# iCliQ_v1.net
KiCad netlist of a schematic drawn in Altium Designer
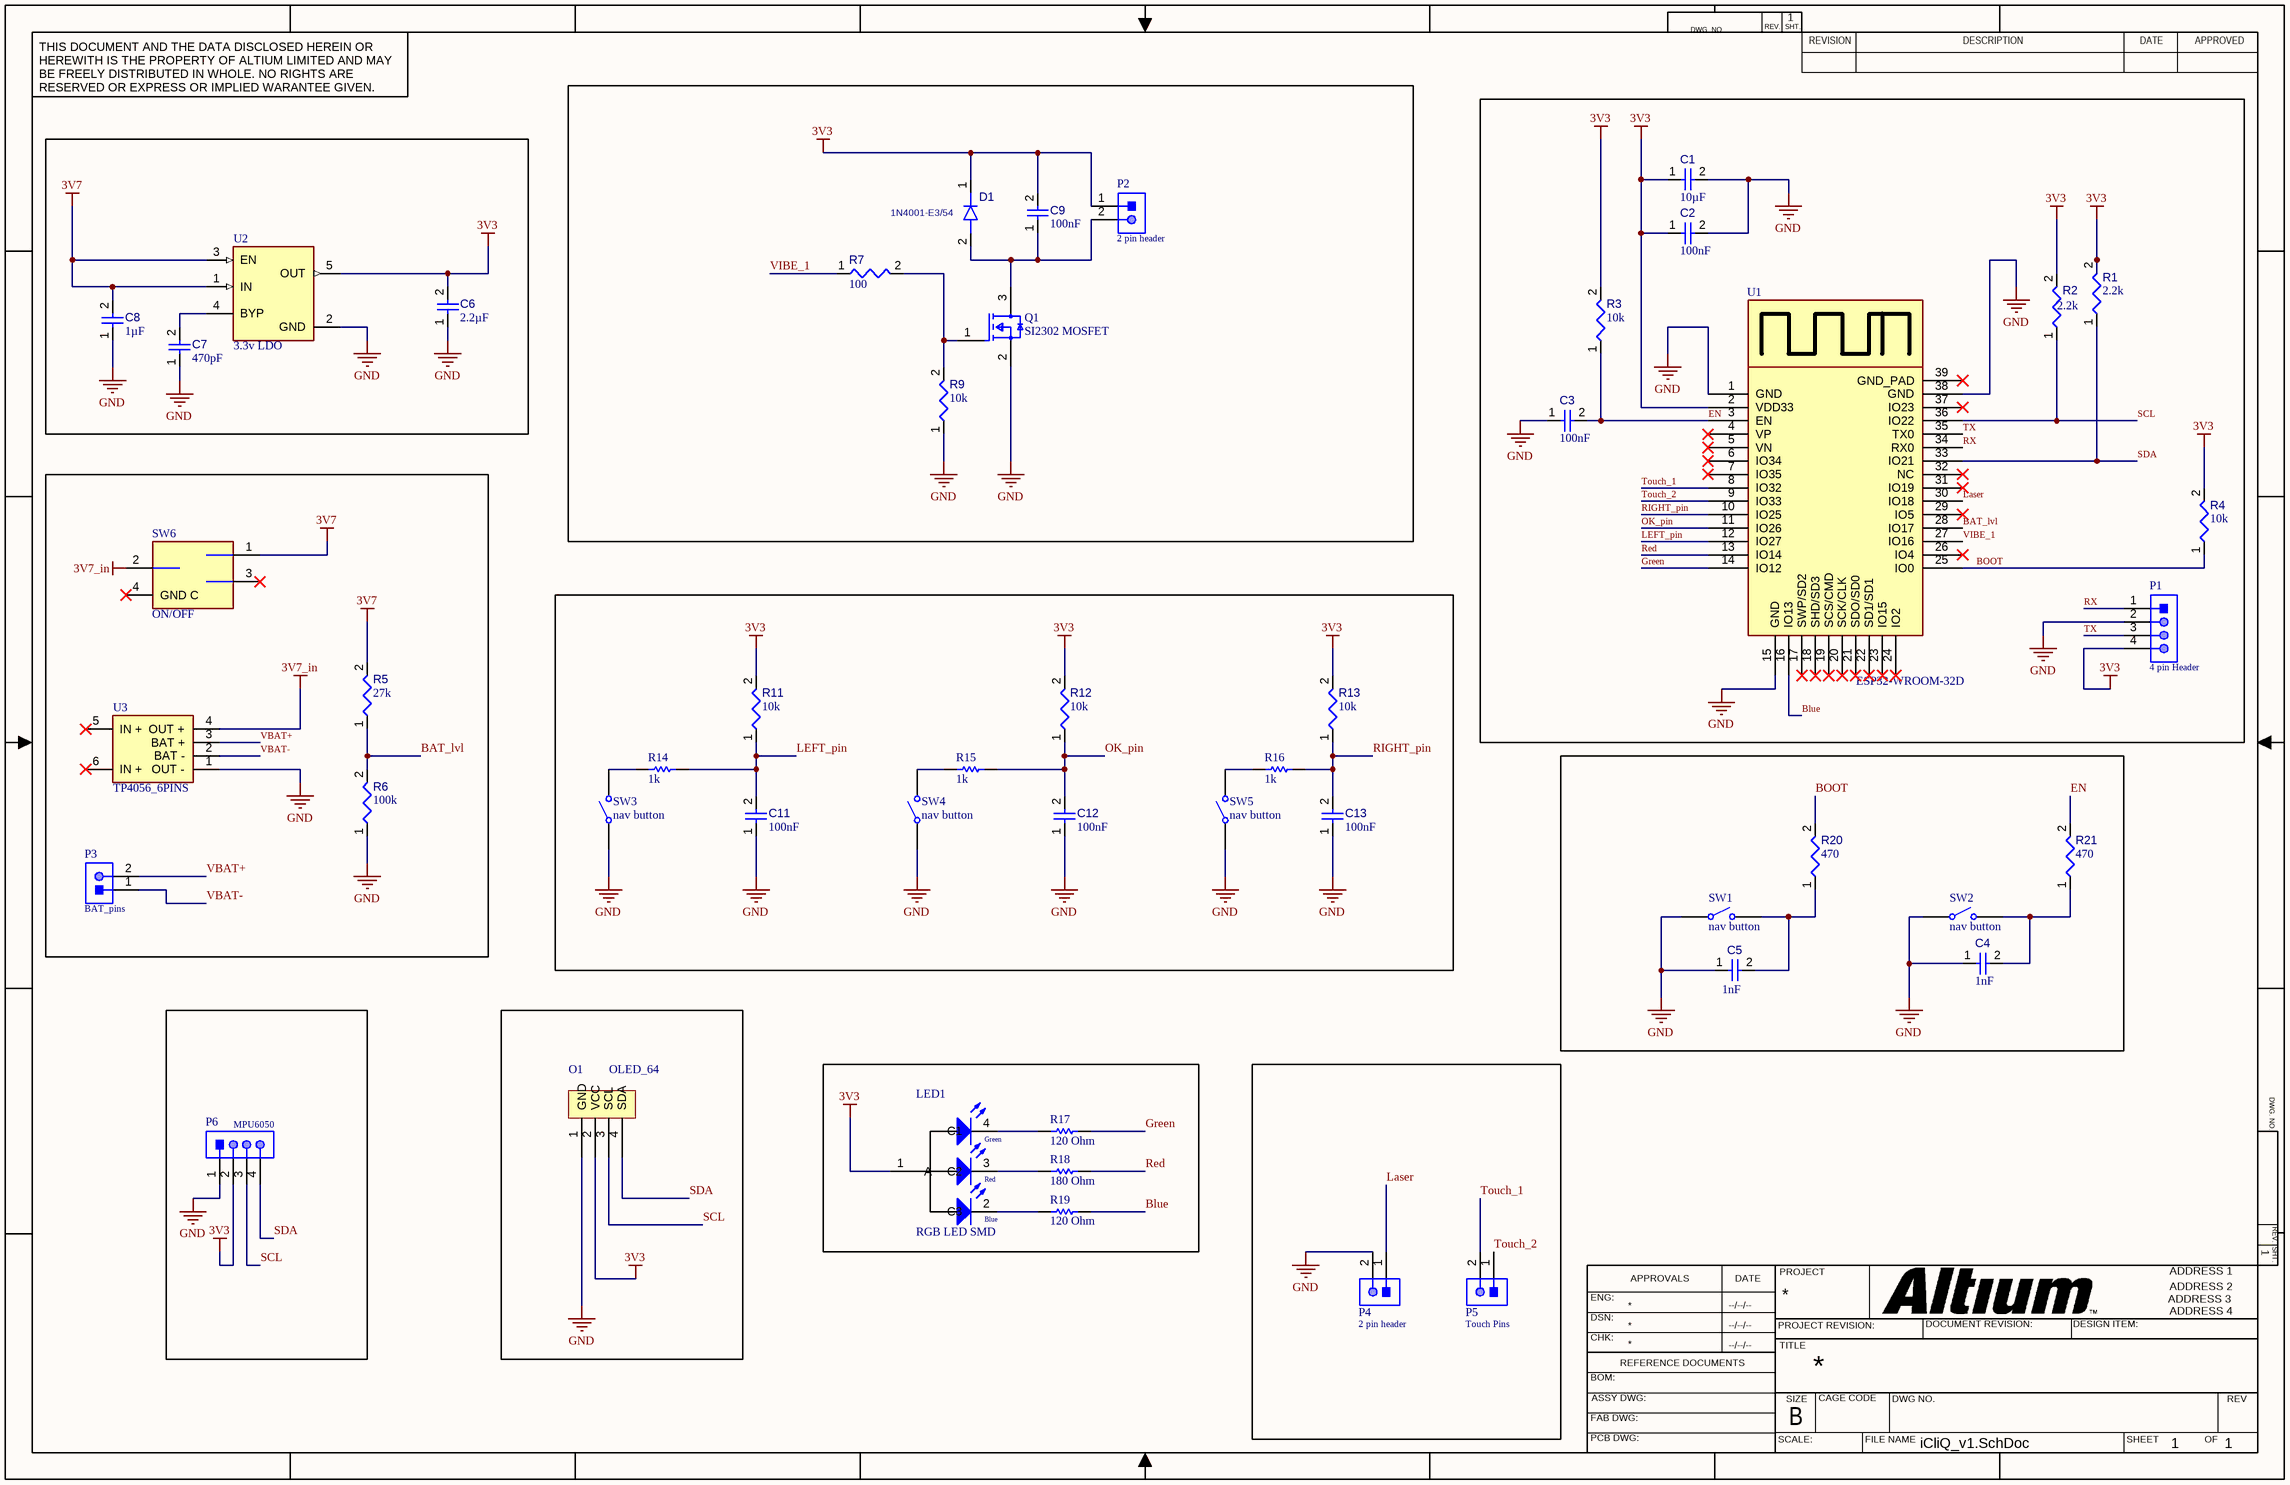
[diagram p0: iCliQ_v1.SchDoc]

(export (version "E")
  (design (tool "Eeschema 10.0.6"))
  (components
    (comp (ref "C1")
      (value "10µF")
      (footprint "FP-C0805C-DG-IPC_A")
      (fields (field (name "Comment") "10uF 10V 0805"))
      (libsource (lib "Company of Noobs - ENTC") (part "CAP-NP-2"))
    )
    (comp (ref "C2")
      (value "100nF")
      (footprint "CAPC2013X95X50LL10T25")
      (description "Chip Capacitor, 100 nF, +/- 10%, 50 V, 0805 (2012 Metric)")
      (fields (field (name "TOLERANCE") "10%") (field (name "Comment") "Capacitor 100 nF +/-10% 50 V 0805"))
      (libsource (lib "Company of Noobs - ENTC") (part "CAP-NP-2"))
    )
    (comp (ref "C3")
      (value "100nF")
      (footprint "CAPC2013X95X50LL10T25")
      (description "Chip Capacitor, 100 nF, +/- 10%, 50 V, 0805 (2012 Metric)")
      (fields (field (name "TOLERANCE") "10%") (field (name "Comment") "Capacitor 100 nF +/-10% 50 V 0805"))
      (libsource (lib "Company of Noobs - ENTC") (part "CAP-NP-2"))
    )
    (comp (ref "C4")
      (value "1nF")
      (footprint "FP-C0805C-DN-IPC_A")
      (fields (field (name "Comment") "1 nF 50V 0805"))
      (libsource (lib "Company of Noobs - ENTC") (part "CAP-NP-2"))
    )
    (comp (ref "C5")
      (value "1nF")
      (footprint "FP-C0805C-DN-IPC_A")
      (fields (field (name "Comment") "1 nF 50V 0805"))
      (libsource (lib "Company of Noobs - ENTC") (part "CAP-NP-2"))
    )
    (comp (ref "C6")
      (value "2.2µF")
      (footprint "FP-C0805C225K4RACAUTO-IPC_A")
      (fields (field (name "Comment") "2.2 uF 0805"))
      (libsource (lib "Company of Noobs - ENTC") (part "CAP-NP-2"))
    )
    (comp (ref "C7")
      (value "470pF")
      (footprint "FP-C0805C-DN-IPC_A")
      (fields (field (name "Comment") "470 pF 0805"))
      (libsource (lib "Company of Noobs - ENTC") (part "CAP-NP-2"))
    )
    (comp (ref "C8")
      (value "1µF")
      (footprint "CAPC2013X140X50LL20T25")
      (fields (field (name "Comment") "1uF 10V 0805"))
      (libsource (lib "Company of Noobs - ENTC") (part "CAP-NP-2"))
    )
    (comp (ref "C9")
      (value "100nF")
      (footprint "CAPC2013X95X50LL10T25")
      (description "Chip Capacitor, 100 nF, +/- 10%, 50 V, 0805 (2012 Metric)")
      (fields (field (name "TOLERANCE") "10%") (field (name "Comment") "Capacitor 100 nF +/-10% 50 V 0805"))
      (libsource (lib "Company of Noobs - ENTC") (part "CAP-NP-2"))
    )
    (comp (ref "C11")
      (value "100nF")
      (footprint "CAPC2013X95X50LL10T25")
      (description "Chip Capacitor, 100 nF, +/- 10%, 50 V, 0805 (2012 Metric)")
      (fields (field (name "TOLERANCE") "10%") (field (name "Comment") "Capacitor 100 nF +/-10% 50 V 0805"))
      (libsource (lib "Company of Noobs - ENTC") (part "CAP-NP-2"))
    )
    (comp (ref "C12")
      (value "100nF")
      (footprint "CAPC2013X95X50LL10T25")
      (description "Chip Capacitor, 100 nF, +/- 10%, 50 V, 0805 (2012 Metric)")
      (fields (field (name "TOLERANCE") "10%") (field (name "Comment") "Capacitor 100 nF +/-10% 50 V 0805"))
      (libsource (lib "Company of Noobs - ENTC") (part "CAP-NP-2"))
    )
    (comp (ref "C13")
      (value "100nF")
      (footprint "CAPC2013X95X50LL10T25")
      (description "Chip Capacitor, 100 nF, +/- 10%, 50 V, 0805 (2012 Metric)")
      (fields (field (name "TOLERANCE") "10%") (field (name "Comment") "Capacitor 100 nF +/-10% 50 V 0805"))
      (libsource (lib "Company of Noobs - ENTC") (part "CAP-NP-2"))
    )
    (comp (ref "D1")
      (value "1N4001-E3/54")
      (footprint "FP-1N4001-E3-54-MFG")
      (description "Rectifier Diode, 1 Phase, 1 Element, 1A, 50V V(RRM), Silicon, DO-204AL")
      (libsource (lib "Company of Noobs - ENTC") (part "DIODE-2"))
    )
    (comp (ref "LED1")
      (value "RGB LED SMD")
      (footprint "3528_A")
      (description "Triple Color LED, Red/green/blue, Water Clear")
      (libsource (lib "Company of Noobs - ENTC") (part "WE-LED_RGB_A1B2R3G4-4"))
    )
    (comp (ref "O1")
      (value "OLED_64")
      (footprint "OLED_SSD1306_64")
      (description "JST (JAPAN SOLDERLESS TERMINALS) - B8B-XH-A (LF)(SN) - HEADER, VERTICAL, 8WAY")
      (fields
        (field (name "MANUFACTURER") "JST")
        (field (name "MANUFACTURER PART NUMBER") "B8B-XH-A(LF)(SN)")
      )
      (libsource (lib "Schlib1") (part "OLED_64"))
    )
    (comp (ref "P1")
      (value "4 pin Header")
      (footprint "61300411121")
      (libsource (lib "") (part "WE-CN-1P-M-R4_1"))
    )
    (comp (ref "P2")
      (value "2 pin header")
      (footprint "61300211121")
      (libsource (lib "") (part "WE-CN-1P-M-R2_2"))
    )
    (comp (ref "P3")
      (value "BAT_pins")
      (footprint "61300211121")
      (libsource (lib "") (part "WE-CN-1P-M-R2_1"))
    )
    (comp (ref "P4")
      (value "2 pin header")
      (footprint "61300211121")
      (libsource (lib "Company of Noobs - ENTC") (part "WE-CN-1P-M-R2"))
    )
    (comp (ref "P5")
      (value "Touch Pins")
      (footprint "61300211121")
      (libsource (lib "Company of Noobs - ENTC") (part "WE-CN-1P-M-R2"))
    )
    (comp (ref "P6")
      (value "MPU6050")
      (footprint "61300411121")
      (libsource (lib "Company of Noobs - ENTC") (part "WE-CN-1P-M-R4"))
    )
    (comp (ref "Q1")
      (value "SI2302 MOSFET")
      (footprint "FP-S-03946-MFG")
      (libsource (lib "Company of Noobs - ENTC") (part "0a9ea7c96deaaede766a5b531c28de0"))
    )
    (comp (ref "R1")
      (value "2.2k")
      (footprint "RESC2013X60X40LL20T25")
      (description "Fixed Resistor, Thin Film, 0.125W, 2200ohm, 100V, 0.5% +/-Tol, 25ppm/Cel, Surface Mount, 0805")
      (fields (field (name "TOLERANCE") "0.5%") (field (name "POWER") "125mW"))
      (libsource (lib "Company of Noobs - ENTC") (part "RES-2"))
    )
    (comp (ref "R2")
      (value "2.2k")
      (footprint "RESC2013X60X40LL20T25")
      (description "Fixed Resistor, Thin Film, 0.125W, 2200ohm, 100V, 0.5% +/-Tol, 25ppm/Cel, Surface Mount, 0805")
      (fields (field (name "TOLERANCE") "0.5%") (field (name "POWER") "125mW"))
      (libsource (lib "Company of Noobs - ENTC") (part "RES-2"))
    )
    (comp (ref "R3")
      (value "10k")
      (footprint "RESC2013X60X35LL10T20")
      (fields
        (field (name "TOLERANCE") "1%")
        (field (name "POWER") "125mW")
        (field (name "Comment") "10K 0805")
      )
      (libsource (lib "Company of Noobs - ENTC") (part "RES-2"))
    )
    (comp (ref "R4")
      (value "10k")
      (footprint "RESC2013X60X35LL10T20")
      (fields
        (field (name "TOLERANCE") "1%")
        (field (name "POWER") "125mW")
        (field (name "Comment") "10K 0805")
      )
      (libsource (lib "Company of Noobs - ENTC") (part "RES-2"))
    )
    (comp (ref "R5")
      (value "27k")
      (footprint "RESC2013X60X40LL20T25")
      (description "Fixed Resistor, Thin Film, 0.125W, 27000ohm, 100V, 0.1% +/-Tol, 25ppm/Cel, Surface Mount, 0805")
      (fields (field (name "POWER") "125mW") (field (name "TOLERANCE") "0.1%"))
      (libsource (lib "Company of Noobs - ENTC") (part "RES-2"))
    )
    (comp (ref "R6")
      (value "100k")
      (footprint "RESC2013X70X40ML20T20")
      (description "Chip Resistor, 100 KOhm, +/- 1%, 0.125 W, -55 to 155 degC, 0805 (2012 Metric)")
      (fields (field (name "POWER") "125mW") (field (name "TOLERANCE") "1%"))
      (libsource (lib "Company of Noobs - ENTC") (part "RES-2"))
    )
    (comp (ref "R7")
      (value "100")
      (footprint "RESC2013X60X40LL20T25")
      (description "Fixed Resistor, Thin Film, 0.125W, 100ohm, 100V, 0.1% +/-Tol, 25ppm/Cel, Surface Mount, 0805")
      (fields (field (name "POWER") "125mW") (field (name "TOLERANCE") "0.1%"))
      (libsource (lib "Company of Noobs - ENTC") (part "RES-2"))
    )
    (comp (ref "R9")
      (value "10k")
      (footprint "RESC2013X60X35LL10T20")
      (fields
        (field (name "TOLERANCE") "1%")
        (field (name "POWER") "125mW")
        (field (name "Comment") "10K 0805")
      )
      (libsource (lib "Company of Noobs - ENTC") (part "RES-2"))
    )
    (comp (ref "R11")
      (value "10k")
      (footprint "RESC2013X60X35LL10T20")
      (fields
        (field (name "TOLERANCE") "1%")
        (field (name "POWER") "125mW")
        (field (name "Comment") "10K 0805")
      )
      (libsource (lib "Company of Noobs - ENTC") (part "RES-2"))
    )
    (comp (ref "R12")
      (value "10k")
      (footprint "RESC2013X60X35LL10T20")
      (fields
        (field (name "TOLERANCE") "1%")
        (field (name "POWER") "125mW")
        (field (name "Comment") "10K 0805")
      )
      (libsource (lib "Company of Noobs - ENTC") (part "RES-2"))
    )
    (comp (ref "R13")
      (value "10k")
      (footprint "RESC2013X60X35LL10T20")
      (fields
        (field (name "TOLERANCE") "1%")
        (field (name "POWER") "125mW")
        (field (name "Comment") "10K 0805")
      )
      (libsource (lib "Company of Noobs - ENTC") (part "RES-2"))
    )
    (comp (ref "R14")
      (value "1k")
      (footprint "RESC2013X70X40NL20T20")
      (fields
        (field (name "TOLERANCE") "5%")
        (field (name "POWER") "500mW")
        (field (name "Comment") "Resistor 1K +/-5% 0805 500 mW.")
      )
      (libsource (lib "Company of Noobs - ENTC") (part "RES"))
    )
    (comp (ref "R15")
      (value "1k")
      (footprint "RESC2013X70X40NL20T20")
      (fields
        (field (name "TOLERANCE") "5%")
        (field (name "POWER") "500mW")
        (field (name "Comment") "Resistor 1K +/-5% 0805 500 mW.")
      )
      (libsource (lib "Company of Noobs - ENTC") (part "RES"))
    )
    (comp (ref "R16")
      (value "1k")
      (footprint "RESC2013X70X40NL20T20")
      (fields
        (field (name "TOLERANCE") "5%")
        (field (name "POWER") "500mW")
        (field (name "Comment") "Resistor 1K +/-5% 0805 500 mW.")
      )
      (libsource (lib "Company of Noobs - ENTC") (part "RES"))
    )
    (comp (ref "R17")
      (value "120 Ohm")
      (footprint "RESC2013X50X35ML15T15")
      (description "Chip Resistor, 0 Ohm, +/- 1%, 125 mW, -55 to 155 degC, 0805 (2012 Metric)")
      (fields (field (name "TOLERANCE") "1%") (field (name "POWER") "125mW"))
      (libsource (lib "") (part "RES-2_1"))
    )
    (comp (ref "R18")
      (value "180 Ohm")
      (footprint "RESC2013X50X35ML15T15")
      (description "Chip Resistor, 0 Ohm, +/- 1%, 125 mW, -55 to 155 degC, 0805 (2012 Metric)")
      (fields (field (name "TOLERANCE") "1%") (field (name "POWER") "125mW"))
      (libsource (lib "") (part "RES-2_1"))
    )
    (comp (ref "R19")
      (value "120 Ohm")
      (footprint "RESC2013X50X35ML15T15")
      (description "Chip Resistor, 0 Ohm, +/- 1%, 125 mW, -55 to 155 degC, 0805 (2012 Metric)")
      (fields (field (name "TOLERANCE") "1%") (field (name "POWER") "125mW"))
      (libsource (lib "") (part "RES-2_1"))
    )
    (comp (ref "R20")
      (value "470")
      (footprint "RESC0805(2012)_L")
      (description "Chip Resistor, 470 Ohms, +/-5%, 125 mW, -55 to 155 degC, 0805")
      (fields (field (name "TOLERANCE") "5%") (field (name "POWER") "125mW"))
      (libsource (lib "Company of Noobs - ENTC") (part "RES-2"))
    )
    (comp (ref "R21")
      (value "470")
      (footprint "RESC0805(2012)_L")
      (description "Chip Resistor, 470 Ohms, +/-5%, 125 mW, -55 to 155 degC, 0805")
      (fields (field (name "TOLERANCE") "5%") (field (name "POWER") "125mW"))
      (libsource (lib "Company of Noobs - ENTC") (part "RES-2"))
    )
    (comp (ref "SW1")
      (value "nav button")
      (footprint "434121050816")
      (libsource (lib "Company of Noobs - ENTC") (part "WE-TACT-SW-2"))
    )
    (comp (ref "SW2")
      (value "nav button")
      (footprint "434121050816")
      (libsource (lib "Company of Noobs - ENTC") (part "WE-TACT-SW-2"))
    )
    (comp (ref "SW3")
      (value "nav button")
      (footprint "434121050816")
      (libsource (lib "Company of Noobs - ENTC") (part "WE-TACT-SW-2"))
    )
    (comp (ref "SW4")
      (value "nav button")
      (footprint "434121050816")
      (libsource (lib "Company of Noobs - ENTC") (part "WE-TACT-SW-2"))
    )
    (comp (ref "SW5")
      (value "nav button")
      (footprint "434121050816")
      (libsource (lib "Company of Noobs - ENTC") (part "WE-TACT-SW-2"))
    )
    (comp (ref "SW6")
      (value "Switch_ALPS_SSSS811101_eec")
      (footprint "ALPS_SSSS811101_0")
      (fields
        (field (name "MANUFACTURER") "ALPS")
        (field (name "MOUSER PART NUMBER") "688-SSSS811101")
        (field (name "PART NUMBER") "ON/OFF")
      )
      (libsource (lib "Switch_ALPS_SSSS811101_eec") (part "Switch_ALPS_SSSS811101_eec"))
    )
    (comp (ref "U1")
      (value "ESP32-WROOM-32D")
      (footprint "ESP32-WROOM-32D")
      (description "Chip SMD 39 Pads Wifi 2.4GHz BLE 4.2 18x25.5mm w/ Antenna.")
      (libsource (lib "Company of Noobs - ENTC") (part "ESP32-WROOM-32D"))
    )
    (comp (ref "U2")
      (value "3.3v LDO")
      (footprint "FP-SOT23-5LD-PL-1-MFG")
      (description "IC REG LDO 3.3V 0.5A SOT23-5")
      (libsource (lib "Company of Noobs - ENTC") (part "16b36b16d6b7b40c29ab14718bc3058"))
    )
    (comp (ref "U3")
      (value "TP4056_6PINS")
      (footprint "TP4056_6PINs")
      (description "MODULE BATTERY CHARGER 6 PINS")
      (fields (field (name "SOURCE") "Random.SchLib"))
      (libsource (lib "Company of Noobs - ENTC") (part "TP4056_6PINS"))
    )
  )
  (nets
    (net (code "1") (name "/BAT_lvl") (class "Default")
      (node (ref "R5") (pin "1") (pinfunction "1_1") (pintype "passive"))
      (node (ref "R6") (pin "2") (pinfunction "2_2") (pintype "passive"))
      (node (ref "U1") (pin "28") (pinfunction "IO17_28") (pintype "passive"))
    )
    (net (code "2") (name "/BOOT") (class "Default")
      (node (ref "R20") (pin "2") (pinfunction "2_2") (pintype "passive"))
      (node (ref "R4") (pin "1") (pinfunction "1_1") (pintype "passive"))
      (node (ref "U1") (pin "25") (pinfunction "IO0_25") (pintype "passive"))
    )
    (net (code "3") (name "/Blue") (class "Default")
      (node (ref "R19") (pin "2") (pinfunction "2_2") (pintype "passive"))
      (node (ref "U1") (pin "16") (pinfunction "IO13_16") (pintype "passive"))
    )
    (net (code "4") (name "/EN") (class "Default")
      (node (ref "C3") (pin "2") (pinfunction "2_2") (pintype "passive"))
      (node (ref "R21") (pin "2") (pinfunction "2_2") (pintype "passive"))
      (node (ref "R3") (pin "1") (pinfunction "1_1") (pintype "passive"))
      (node (ref "U1") (pin "3") (pinfunction "EN_3") (pintype "passive"))
    )
    (net (code "5") (name "/Green") (class "Default")
      (node (ref "R17") (pin "2") (pinfunction "2_2") (pintype "passive"))
      (node (ref "U1") (pin "14") (pinfunction "IO12_14") (pintype "passive"))
    )
    (net (code "6") (name "/LEFT_pin") (class "Default")
      (node (ref "C11") (pin "2") (pinfunction "2_2") (pintype "passive"))
      (node (ref "R11") (pin "1") (pinfunction "1_1") (pintype "passive"))
      (node (ref "R14") (pin "2") (pinfunction "2_2") (pintype "passive"))
      (node (ref "U1") (pin "12") (pinfunction "IO27_12") (pintype "passive"))
    )
    (net (code "7") (name "/Laser") (class "Default")
      (node (ref "P4") (pin "1") (pinfunction "1_1") (pintype "passive"))
      (node (ref "U1") (pin "30") (pinfunction "IO18_30") (pintype "passive"))
    )
    (net (code "8") (name "/OK_pin") (class "Default")
      (node (ref "C12") (pin "2") (pinfunction "2_2") (pintype "passive"))
      (node (ref "R12") (pin "1") (pinfunction "1_1") (pintype "passive"))
      (node (ref "R15") (pin "2") (pinfunction "2_2") (pintype "passive"))
      (node (ref "U1") (pin "11") (pinfunction "IO26_11") (pintype "passive"))
    )
    (net (code "9") (name "/RIGHT_pin") (class "Default")
      (node (ref "C13") (pin "2") (pinfunction "2_2") (pintype "passive"))
      (node (ref "R13") (pin "1") (pinfunction "1_1") (pintype "passive"))
      (node (ref "R16") (pin "2") (pinfunction "2_2") (pintype "passive"))
      (node (ref "U1") (pin "10") (pinfunction "IO25_10") (pintype "passive"))
    )
    (net (code "10") (name "/RX") (class "Default")
      (node (ref "P1") (pin "1") (pinfunction "1_1") (pintype "passive"))
      (node (ref "U1") (pin "34") (pinfunction "RX0_34") (pintype "passive"))
    )
    (net (code "11") (name "/Red") (class "Default")
      (node (ref "R18") (pin "2") (pinfunction "2_2") (pintype "passive"))
      (node (ref "U1") (pin "13") (pinfunction "IO14_13") (pintype "passive"))
    )
    (net (code "12") (name "/SCL") (class "Default")
      (node (ref "O1") (pin "3") (pinfunction "SCL_3") (pintype "passive"))
      (node (ref "P6") (pin "3") (pinfunction "3_3") (pintype "passive"))
      (node (ref "R2") (pin "1") (pinfunction "1_1") (pintype "passive"))
      (node (ref "U1") (pin "36") (pinfunction "IO22_36") (pintype "passive"))
    )
    (net (code "13") (name "/SDA") (class "Default")
      (node (ref "O1") (pin "4") (pinfunction "SDA_4") (pintype "passive"))
      (node (ref "P6") (pin "4") (pinfunction "4_4") (pintype "passive"))
      (node (ref "R1") (pin "1") (pinfunction "1_1") (pintype "passive"))
      (node (ref "U1") (pin "33") (pinfunction "IO21_33") (pintype "passive"))
    )
    (net (code "14") (name "/TX") (class "Default")
      (node (ref "P1") (pin "3") (pinfunction "3_3") (pintype "passive"))
      (node (ref "U1") (pin "35") (pinfunction "TX0_35") (pintype "passive"))
    )
    (net (code "15") (name "/Touch_1") (class "Default")
      (node (ref "P5") (pin "2") (pinfunction "2_2") (pintype "passive"))
      (node (ref "U1") (pin "8") (pinfunction "IO32_8") (pintype "passive"))
    )
    (net (code "16") (name "/Touch_2") (class "Default")
      (node (ref "P5") (pin "1") (pinfunction "1_1") (pintype "passive"))
      (node (ref "U1") (pin "9") (pinfunction "IO33_9") (pintype "passive"))
    )
    (net (code "17") (name "/VBAT+") (class "Default")
      (node (ref "P3") (pin "2") (pinfunction "2_2") (pintype "passive"))
      (node (ref "U3") (pin "3") (pinfunction "BAT_+_3") (pintype "passive"))
    )
    (net (code "18") (name "/VBAT-") (class "Default")
      (node (ref "P3") (pin "1") (pinfunction "1_1") (pintype "passive"))
      (node (ref "U3") (pin "2") (pinfunction "BAT_-_2") (pintype "passive"))
    )
    (net (code "19") (name "/VIBE_1") (class "Default")
      (node (ref "R7") (pin "1") (pinfunction "1_1") (pintype "passive"))
      (node (ref "U1") (pin "27") (pinfunction "IO16_27") (pintype "passive"))
    )
    (net (code "20") (name "3V3") (class "Default")
      (node (ref "C1") (pin "1") (pinfunction "1_1") (pintype "passive"))
      (node (ref "C2") (pin "1") (pinfunction "1_1") (pintype "passive"))
      (node (ref "C6") (pin "2") (pinfunction "2_2") (pintype "passive"))
      (node (ref "C9") (pin "2") (pinfunction "2_2") (pintype "passive"))
      (node (ref "D1") (pin "1") (pinfunction "K_1") (pintype "passive"))
      (node (ref "LED1") (pin "1") (pinfunction "A_1") (pintype "passive"))
      (node (ref "O1") (pin "2") (pinfunction "VCC_2") (pintype "passive"))
      (node (ref "P1") (pin "4") (pinfunction "4_4") (pintype "passive"))
      (node (ref "P2") (pin "1") (pinfunction "1_1") (pintype "passive"))
      (node (ref "P6") (pin "2") (pinfunction "2_2") (pintype "passive"))
      (node (ref "R1") (pin "2") (pinfunction "2_2") (pintype "passive"))
      (node (ref "R11") (pin "2") (pinfunction "2_2") (pintype "passive"))
      (node (ref "R12") (pin "2") (pinfunction "2_2") (pintype "passive"))
      (node (ref "R13") (pin "2") (pinfunction "2_2") (pintype "passive"))
      (node (ref "R2") (pin "2") (pinfunction "2_2") (pintype "passive"))
      (node (ref "R3") (pin "2") (pinfunction "2_2") (pintype "passive"))
      (node (ref "R4") (pin "2") (pinfunction "2_2") (pintype "passive"))
      (node (ref "U1") (pin "2") (pinfunction "VDD33_2") (pintype "passive"))
      (node (ref "U2") (pin "5") (pinfunction "OUT_5") (pintype "output"))
    )
    (net (code "21") (name "3V7") (class "Default")
      (node (ref "C8") (pin "2") (pinfunction "2_2") (pintype "passive"))
      (node (ref "R5") (pin "2") (pinfunction "2_2") (pintype "passive"))
      (node (ref "SW6") (pin "1") (pinfunction "1_1") (pintype "passive"))
      (node (ref "U2") (pin "1") (pinfunction "IN_1") (pintype "input"))
      (node (ref "U2") (pin "3") (pinfunction "EN_3") (pintype "input"))
    )
    (net (code "22") (name "3V7_in") (class "Default")
      (node (ref "SW6") (pin "2") (pinfunction "C_2") (pintype "passive"))
      (node (ref "U3") (pin "4") (pinfunction "OUT_+_4") (pintype "passive"))
    )
    (net (code "23") (name "GND") (class "Default")
      (node (ref "C1") (pin "2") (pinfunction "2_2") (pintype "passive"))
      (node (ref "C11") (pin "1") (pinfunction "1_1") (pintype "passive"))
      (node (ref "C12") (pin "1") (pinfunction "1_1") (pintype "passive"))
      (node (ref "C13") (pin "1") (pinfunction "1_1") (pintype "passive"))
      (node (ref "C2") (pin "2") (pinfunction "2_2") (pintype "passive"))
      (node (ref "C3") (pin "1") (pinfunction "1_1") (pintype "passive"))
      (node (ref "C4") (pin "1") (pinfunction "1_1") (pintype "passive"))
      (node (ref "C5") (pin "1") (pinfunction "1_1") (pintype "passive"))
      (node (ref "C6") (pin "1") (pinfunction "1_1") (pintype "passive"))
      (node (ref "C7") (pin "1") (pinfunction "1_1") (pintype "passive"))
      (node (ref "C8") (pin "1") (pinfunction "1_1") (pintype "passive"))
      (node (ref "O1") (pin "1") (pinfunction "GND_1") (pintype "passive"))
      (node (ref "P1") (pin "2") (pinfunction "2_2") (pintype "passive"))
      (node (ref "P4") (pin "2") (pinfunction "2_2") (pintype "passive"))
      (node (ref "P6") (pin "1") (pinfunction "1_1") (pintype "passive"))
      (node (ref "Q1") (pin "2") (pinfunction "S_2") (pintype "passive"))
      (node (ref "R6") (pin "1") (pinfunction "1_1") (pintype "passive"))
      (node (ref "R9") (pin "1") (pinfunction "1_1") (pintype "passive"))
      (node (ref "SW1") (pin "1") (pinfunction "1_1") (pintype "passive"))
      (node (ref "SW2") (pin "1") (pinfunction "1_1") (pintype "passive"))
      (node (ref "SW3") (pin "1") (pinfunction "1_1") (pintype "passive"))
      (node (ref "SW4") (pin "1") (pinfunction "1_1") (pintype "passive"))
      (node (ref "SW5") (pin "1") (pinfunction "1_1") (pintype "passive"))
      (node (ref "U1") (pin "1") (pinfunction "GND_1") (pintype "passive"))
      (node (ref "U1") (pin "15") (pinfunction "GND_15") (pintype "passive"))
      (node (ref "U1") (pin "38") (pinfunction "GND_38") (pintype "passive"))
      (node (ref "U2") (pin "2") (pinfunction "GND_2") (pintype "power_in"))
      (node (ref "U3") (pin "1") (pinfunction "OUT_-_1") (pintype "passive"))
    )
    (net (code "24") (name "Net-(C4-Pad2)") (class "Default")
      (node (ref "C4") (pin "2") (pinfunction "2_2") (pintype "passive"))
      (node (ref "R21") (pin "1") (pinfunction "1_1") (pintype "passive"))
      (node (ref "SW2") (pin "2") (pinfunction "2_2") (pintype "passive"))
    )
    (net (code "25") (name "Net-(C5-Pad2)") (class "Default")
      (node (ref "C5") (pin "2") (pinfunction "2_2") (pintype "passive"))
      (node (ref "R20") (pin "1") (pinfunction "1_1") (pintype "passive"))
      (node (ref "SW1") (pin "2") (pinfunction "2_2") (pintype "passive"))
    )
    (net (code "26") (name "Net-(D1-A)") (class "Default")
      (node (ref "C9") (pin "1") (pinfunction "1_1") (pintype "passive"))
      (node (ref "D1") (pin "2") (pinfunction "A_2") (pintype "passive"))
      (node (ref "P2") (pin "2") (pinfunction "2_2") (pintype "passive"))
      (node (ref "Q1") (pin "3") (pinfunction "D_3") (pintype "passive"))
    )
    (net (code "27") (name "Net-(LED1-C1)") (class "Default")
      (node (ref "LED1") (pin "4") (pinfunction "C1_4") (pintype "passive"))
      (node (ref "R17") (pin "1") (pinfunction "1_1") (pintype "passive"))
    )
    (net (code "28") (name "Net-(LED1-C2)") (class "Default")
      (node (ref "LED1") (pin "3") (pinfunction "C2_3") (pintype "passive"))
      (node (ref "R18") (pin "1") (pinfunction "1_1") (pintype "passive"))
    )
    (net (code "29") (name "Net-(LED1-C3)") (class "Default")
      (node (ref "LED1") (pin "2") (pinfunction "C3_2") (pintype "passive"))
      (node (ref "R19") (pin "1") (pinfunction "1_1") (pintype "passive"))
    )
    (net (code "30") (name "Net-(Q1-G)") (class "Default")
      (node (ref "Q1") (pin "1") (pinfunction "G_1") (pintype "passive"))
      (node (ref "R7") (pin "2") (pinfunction "2_2") (pintype "passive"))
      (node (ref "R9") (pin "2") (pinfunction "2_2") (pintype "passive"))
    )
    (net (code "31") (name "Net-(R14-Pad1)") (class "Default")
      (node (ref "R14") (pin "1") (pinfunction "1_1") (pintype "passive"))
      (node (ref "SW3") (pin "2") (pinfunction "2_2") (pintype "passive"))
    )
    (net (code "32") (name "Net-(R15-Pad1)") (class "Default")
      (node (ref "R15") (pin "1") (pinfunction "1_1") (pintype "passive"))
      (node (ref "SW4") (pin "2") (pinfunction "2_2") (pintype "passive"))
    )
    (net (code "33") (name "Net-(R16-Pad1)") (class "Default")
      (node (ref "R16") (pin "1") (pinfunction "1_1") (pintype "passive"))
      (node (ref "SW5") (pin "2") (pinfunction "2_2") (pintype "passive"))
    )
    (net (code "34") (name "Net-(U2-BYP)") (class "Default")
      (node (ref "C7") (pin "2") (pinfunction "2_2") (pintype "passive"))
      (node (ref "U2") (pin "4") (pinfunction "BYP_4") (pintype "passive"))
    )
    (net (code "35") (name "unconnected-(SW6-GND_C-Pad4)") (class "Default")
      (node (ref "SW6") (pin "4") (pinfunction "GND_C_4") (pintype "passive+no_connect"))
    )
    (net (code "36") (name "unconnected-(SW6-Pad3)") (class "Default")
      (node (ref "SW6") (pin "3") (pinfunction "3_3") (pintype "passive+no_connect"))
    )
    (net (code "37") (name "unconnected-(U1-GND_PAD-Pad39)") (class "Default")
      (node (ref "U1") (pin "39") (pinfunction "GND_PAD_39") (pintype "passive+no_connect"))
    )
    (net (code "38") (name "unconnected-(U1-IO2-Pad24)") (class "Default")
      (node (ref "U1") (pin "24") (pinfunction "IO2_24") (pintype "passive+no_connect"))
    )
    (net (code "39") (name "unconnected-(U1-IO4-Pad26)") (class "Default")
      (node (ref "U1") (pin "26") (pinfunction "IO4_26") (pintype "passive+no_connect"))
    )
    (net (code "40") (name "unconnected-(U1-IO5-Pad29)") (class "Default")
      (node (ref "U1") (pin "29") (pinfunction "IO5_29") (pintype "passive+no_connect"))
    )
    (net (code "41") (name "unconnected-(U1-IO15-Pad23)") (class "Default")
      (node (ref "U1") (pin "23") (pinfunction "IO15_23") (pintype "passive+no_connect"))
    )
    (net (code "42") (name "unconnected-(U1-IO19-Pad31)") (class "Default")
      (node (ref "U1") (pin "31") (pinfunction "IO19_31") (pintype "passive+no_connect"))
    )
    (net (code "43") (name "unconnected-(U1-IO23-Pad37)") (class "Default")
      (node (ref "U1") (pin "37") (pinfunction "IO23_37") (pintype "passive+no_connect"))
    )
    (net (code "44") (name "unconnected-(U1-IO34-Pad6)") (class "Default")
      (node (ref "U1") (pin "6") (pinfunction "IO34_6") (pintype "passive+no_connect"))
    )
    (net (code "45") (name "unconnected-(U1-IO35-Pad7)") (class "Default")
      (node (ref "U1") (pin "7") (pinfunction "IO35_7") (pintype "passive+no_connect"))
    )
    (net (code "46") (name "unconnected-(U1-NC-Pad32)") (class "Default")
      (node (ref "U1") (pin "32") (pinfunction "NC_32") (pintype "passive+no_connect"))
    )
    (net (code "47") (name "unconnected-(U1-SCK{slash}CLK-Pad20)") (class "Default")
      (node (ref "U1") (pin "20") (pinfunction "SCK/CLK_20") (pintype "passive+no_connect"))
    )
    (net (code "48") (name "unconnected-(U1-SCS{slash}CMD-Pad19)") (class "Default")
      (node (ref "U1") (pin "19") (pinfunction "SCS/CMD_19") (pintype "passive+no_connect"))
    )
    (net (code "49") (name "unconnected-(U1-SD1{slash}SD1-Pad22)") (class "Default")
      (node (ref "U1") (pin "22") (pinfunction "SD1/SD1_22") (pintype "passive+no_connect"))
    )
    (net (code "50") (name "unconnected-(U1-SDO{slash}SD0-Pad21)") (class "Default")
      (node (ref "U1") (pin "21") (pinfunction "SDO/SD0_21") (pintype "passive+no_connect"))
    )
    (net (code "51") (name "unconnected-(U1-SHD{slash}SD3-Pad18)") (class "Default")
      (node (ref "U1") (pin "18") (pinfunction "SHD/SD3_18") (pintype "passive+no_connect"))
    )
    (net (code "52") (name "unconnected-(U1-SWP{slash}SD2-Pad17)") (class "Default")
      (node (ref "U1") (pin "17") (pinfunction "SWP/SD2_17") (pintype "passive+no_connect"))
    )
    (net (code "53") (name "unconnected-(U1-VN-Pad5)") (class "Default")
      (node (ref "U1") (pin "5") (pinfunction "VN_5") (pintype "passive+no_connect"))
    )
    (net (code "54") (name "unconnected-(U1-VP-Pad4)") (class "Default")
      (node (ref "U1") (pin "4") (pinfunction "VP_4") (pintype "passive+no_connect"))
    )
    (net (code "55") (name "unconnected-(U3-IN_+-Pad5)") (class "Default")
      (node (ref "U3") (pin "5") (pinfunction "IN_+_5") (pintype "passive+no_connect"))
    )
    (net (code "56") (name "unconnected-(U3-IN_+-Pad6)") (class "Default")
      (node (ref "U3") (pin "6") (pinfunction "IN_+_6") (pintype "passive+no_connect"))
    )
  )
)
